# Executive_12V_B.net
KiCad netlist of a schematic drawn in EAGLE
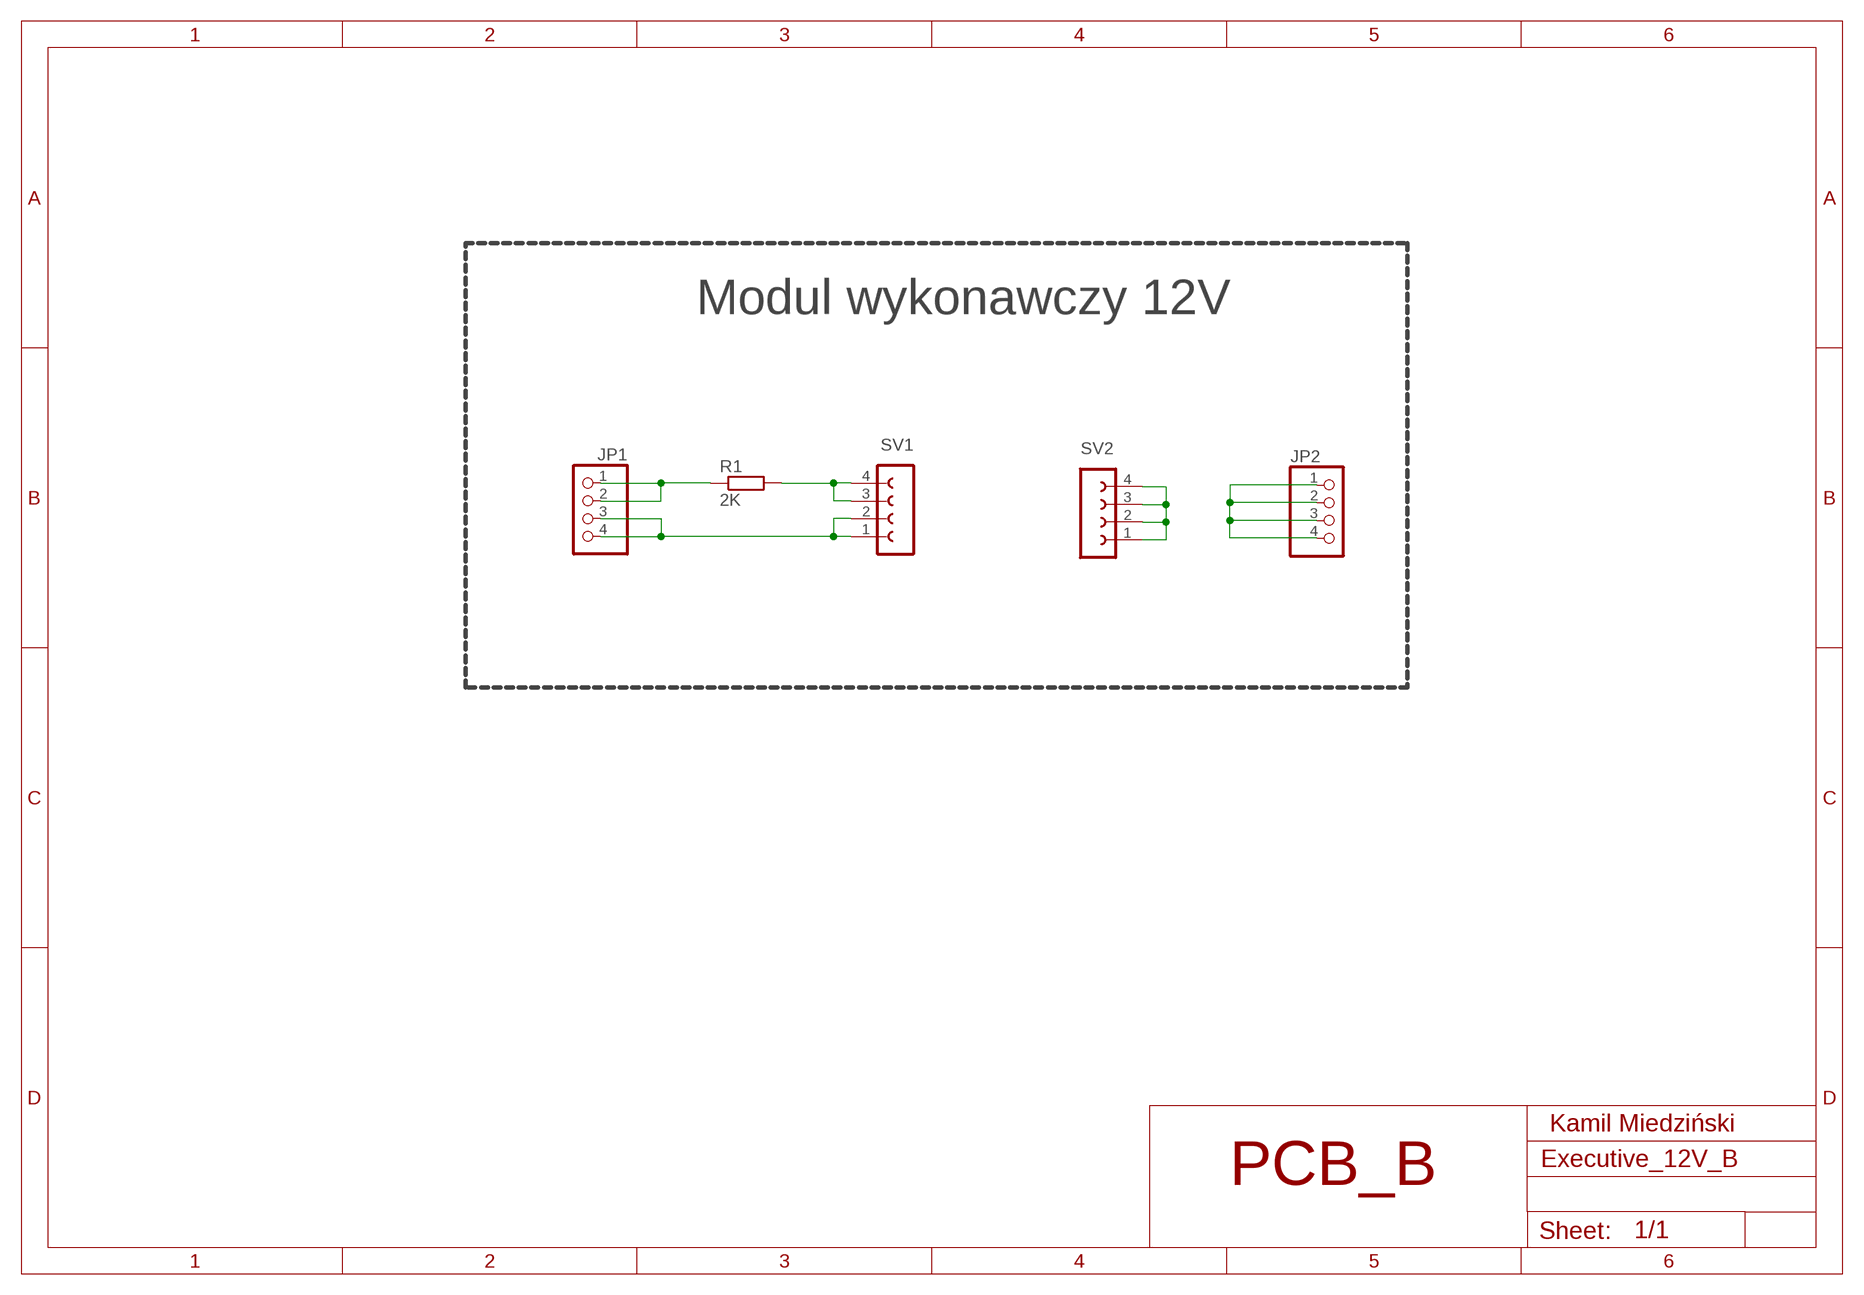
[diagram p0: schematic, sheet 1]

(export (version "E")
  (design (tool "Eeschema 10.0.6"))
  (components
    (comp (ref "JP1")
      (value "PINHD-1X41X04H")
      (footprint "eagle-import:1X04H")
      (libsource (lib "eagle-import") (part "PINHD-1X41X04H"))
    )
    (comp (ref "JP2")
      (value "PINHD-1X41X04H")
      (footprint "eagle-import:1X04H")
      (libsource (lib "eagle-import") (part "PINHD-1X41X04H"))
    )
    (comp (ref "R1")
      (value "2K")
      (footprint "eagle-import:0207_10")
      (libsource (lib "eagle-import") (part "R-EU_0207/10"))
    )
    (comp (ref "SV1")
      (value "FE04-1")
      (footprint "eagle-import:FE04-1")
      (libsource (lib "eagle-import") (part "FE04-1"))
    )
    (comp (ref "SV2")
      (value "FE04-1")
      (footprint "eagle-import:FE04-1")
      (libsource (lib "eagle-import") (part "FE04-1"))
    )
  )
  (nets
    (net (code "1") (name "Net-(JP1-Pad1)") (class "Default")
      (node (ref "JP1") (pin "1") (pinfunction "1_1") (pintype "passive"))
      (node (ref "JP1") (pin "2") (pinfunction "2_2") (pintype "passive"))
      (node (ref "R1") (pin "1") (pinfunction "1_1") (pintype "passive"))
    )
    (net (code "2") (name "Net-(JP2-Pad1)") (class "Default")
      (node (ref "JP2") (pin "1") (pinfunction "1_1") (pintype "passive"))
      (node (ref "JP2") (pin "2") (pinfunction "2_2") (pintype "passive"))
      (node (ref "JP2") (pin "3") (pinfunction "3_3") (pintype "passive"))
      (node (ref "JP2") (pin "4") (pinfunction "4_4") (pintype "passive"))
    )
    (net (code "3") (name "Net-(SV1-2)") (class "Default")
      (node (ref "JP1") (pin "3") (pinfunction "3_3") (pintype "passive"))
      (node (ref "JP1") (pin "4") (pinfunction "4_4") (pintype "passive"))
      (node (ref "SV1") (pin "1") (pinfunction "2_1") (pintype "passive"))
      (node (ref "SV1") (pin "2") (pinfunction "3_2") (pintype "passive"))
    )
    (net (code "4") (name "Net-(SV1-4)") (class "Default")
      (node (ref "R1") (pin "2") (pinfunction "2_2") (pintype "passive"))
      (node (ref "SV1") (pin "3") (pinfunction "4_3") (pintype "passive"))
      (node (ref "SV1") (pin "4") (pinfunction "5_4") (pintype "passive"))
    )
    (net (code "5") (name "Net-(SV2-2)") (class "Default")
      (node (ref "SV2") (pin "1") (pinfunction "2_1") (pintype "passive"))
      (node (ref "SV2") (pin "2") (pinfunction "3_2") (pintype "passive"))
      (node (ref "SV2") (pin "3") (pinfunction "4_3") (pintype "passive"))
      (node (ref "SV2") (pin "4") (pinfunction "5_4") (pintype "passive"))
    )
  )
)
